# Spresense_PLC__V1.net
KiCad netlist of a schematic drawn in EAGLE
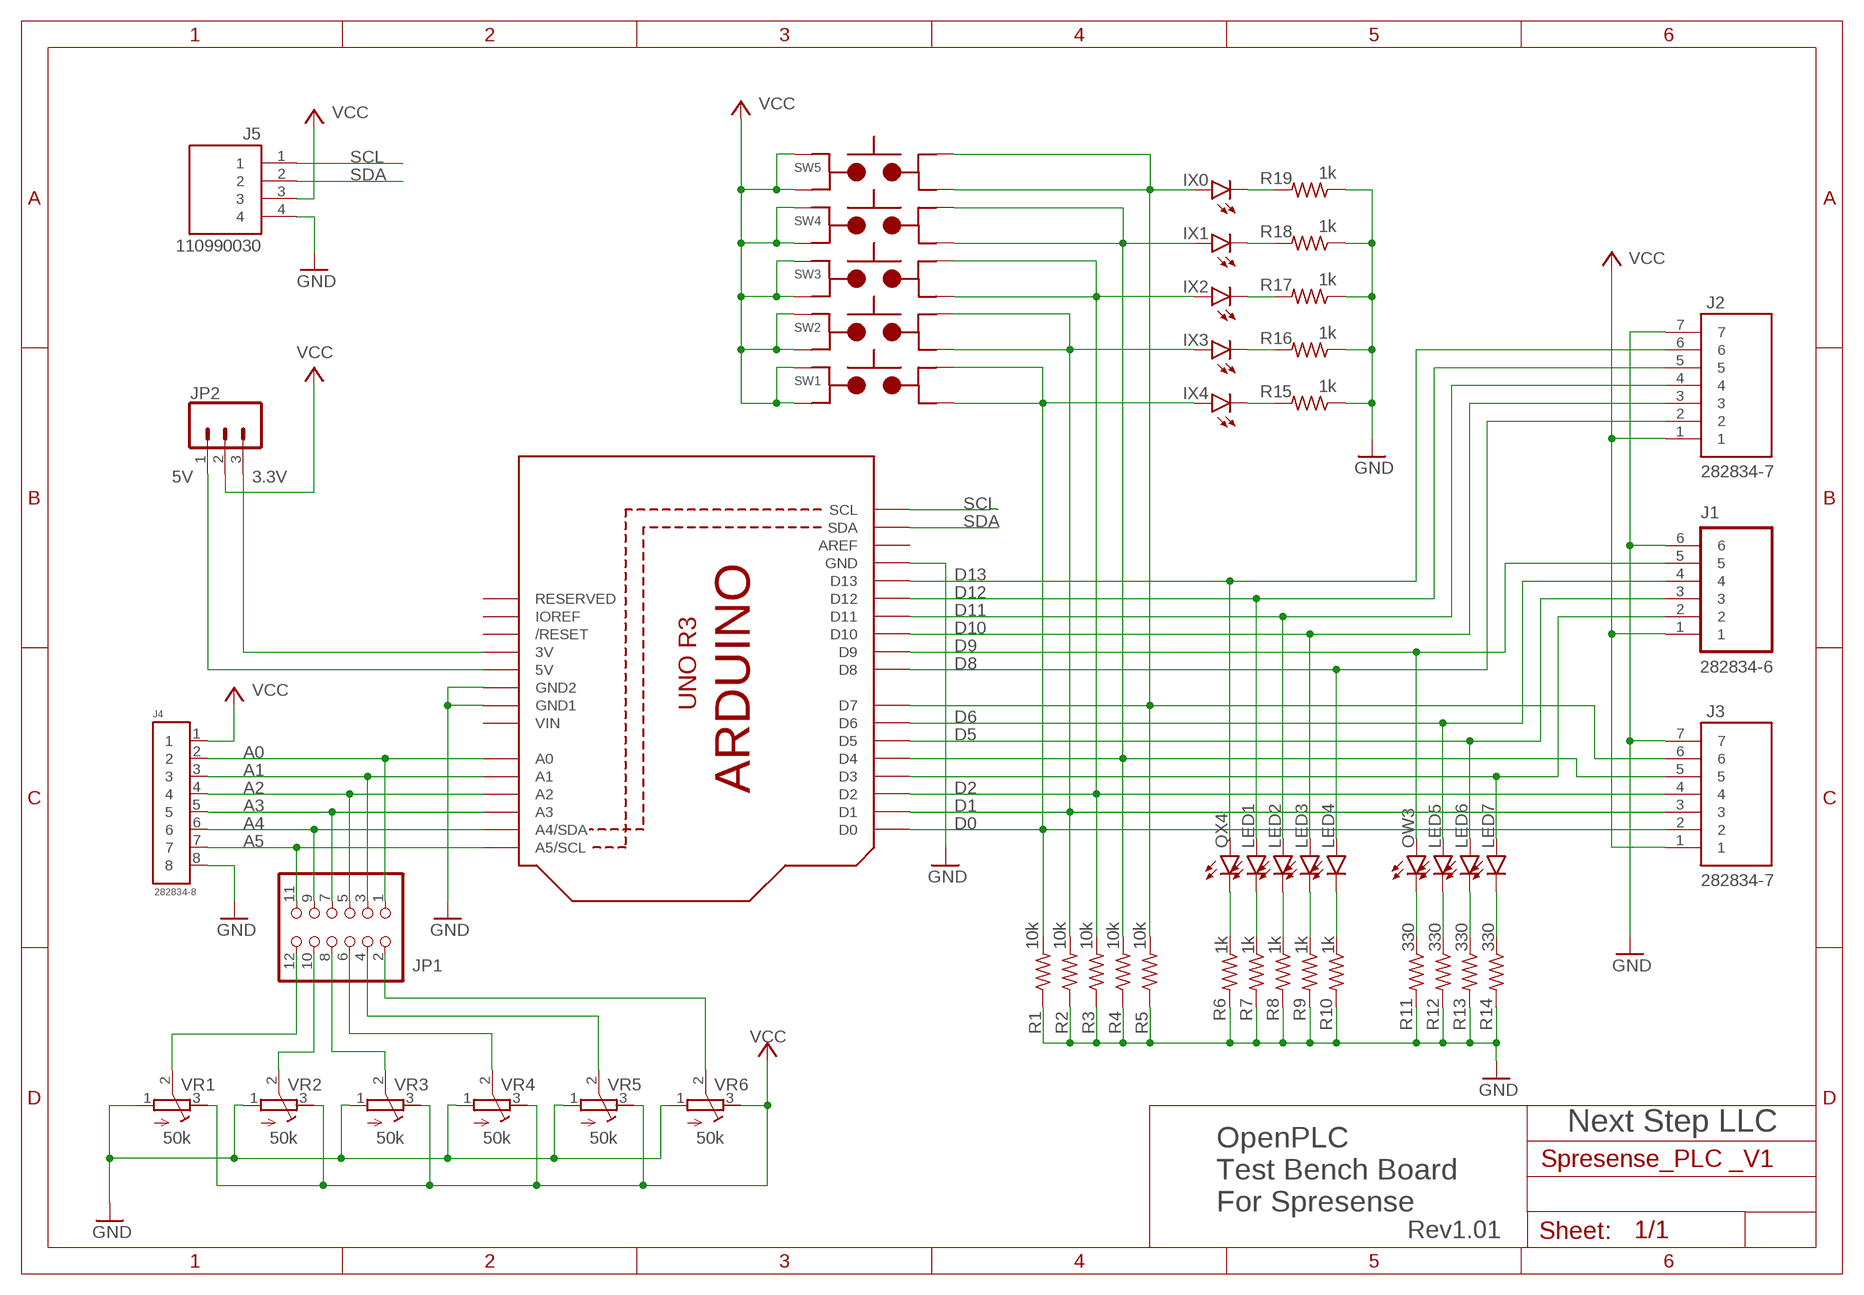
[diagram p0: schematic, sheet 1]

(export (version "E")
  (design (tool "Eeschema 10.0.6"))
  (components
    (comp (ref "IX0")
      (value "LEDCHIP-LED0603")
      (footprint "eagle-import:CHIP-LED0603")
      (libsource (lib "eagle-import") (part "LEDCHIP-LED0603"))
    )
    (comp (ref "IX1")
      (value "LEDCHIP-LED0603")
      (footprint "eagle-import:CHIP-LED0603")
      (libsource (lib "eagle-import") (part "LEDCHIP-LED0603"))
    )
    (comp (ref "IX2")
      (value "LEDCHIP-LED0603")
      (footprint "eagle-import:CHIP-LED0603")
      (libsource (lib "eagle-import") (part "LEDCHIP-LED0603"))
    )
    (comp (ref "IX3")
      (value "LEDCHIP-LED0603")
      (footprint "eagle-import:CHIP-LED0603")
      (libsource (lib "eagle-import") (part "LEDCHIP-LED0603"))
    )
    (comp (ref "IX4")
      (value "LEDCHIP-LED0603")
      (footprint "eagle-import:CHIP-LED0603")
      (libsource (lib "eagle-import") (part "LEDCHIP-LED0603"))
    )
    (comp (ref "J1")
      (value "282834-6")
      (footprint "eagle-import:TE_282834-6")
      (fields (field (name "MF") "TE Connectivity"))
      (libsource (lib "eagle-import") (part "282834-6"))
    )
    (comp (ref "J2")
      (value "282834-7")
      (footprint "eagle-import:TE_282834-7")
      (fields (field (name "MF") "TE Connectivity"))
      (libsource (lib "eagle-import") (part "282834-7"))
    )
    (comp (ref "J3")
      (value "282834-7")
      (footprint "eagle-import:TE_282834-7")
      (fields (field (name "MF") "TE Connectivity"))
      (libsource (lib "eagle-import") (part "282834-7"))
    )
    (comp (ref "J4")
      (value "282834-8")
      (footprint "eagle-import:HDRV8W85P254_8X1_2078X650X1000")
      (fields (field (name "MF") "TE Connectivity"))
      (libsource (lib "eagle-import") (part "282834-8"))
    )
    (comp (ref "J5")
      (value "110990030")
      (footprint "eagle-import:SEEED_110990030")
      (fields (field (name "MF") "Seeed Technology Co., Ltd"))
      (libsource (lib "eagle-import") (part "110990030"))
    )
    (comp (ref "JP1")
      (value "PINHD-2X6")
      (footprint "eagle-import:2X06")
      (libsource (lib "eagle-import") (part "PINHD-2X6"))
    )
    (comp (ref "JP2")
      (value "455-1750-1-ND")
      (footprint "eagle-import:1X03")
      (libsource (lib "eagle-import") (part "CONN_03"))
    )
    (comp (ref "LED1")
      (value "LEDCHIP-LED0603")
      (footprint "eagle-import:CHIP-LED0603")
      (libsource (lib "eagle-import") (part "LEDCHIP-LED0603"))
    )
    (comp (ref "LED2")
      (value "LEDCHIP-LED0603")
      (footprint "eagle-import:CHIP-LED0603")
      (libsource (lib "eagle-import") (part "LEDCHIP-LED0603"))
    )
    (comp (ref "LED3")
      (value "LEDCHIP-LED0603")
      (footprint "eagle-import:CHIP-LED0603")
      (libsource (lib "eagle-import") (part "LEDCHIP-LED0603"))
    )
    (comp (ref "LED4")
      (value "LEDCHIP-LED0603")
      (footprint "eagle-import:CHIP-LED0603")
      (libsource (lib "eagle-import") (part "LEDCHIP-LED0603"))
    )
    (comp (ref "LED5")
      (value "LEDCHIP-LED0603")
      (footprint "eagle-import:CHIP-LED0603")
      (libsource (lib "eagle-import") (part "LEDCHIP-LED0603"))
    )
    (comp (ref "LED6")
      (value "LEDCHIP-LED0603")
      (footprint "eagle-import:CHIP-LED0603")
      (libsource (lib "eagle-import") (part "LEDCHIP-LED0603"))
    )
    (comp (ref "LED7")
      (value "LEDCHIP-LED0603")
      (footprint "eagle-import:CHIP-LED0603")
      (libsource (lib "eagle-import") (part "LEDCHIP-LED0603"))
    )
    (comp (ref "OW3")
      (value "LEDCHIP-LED0603")
      (footprint "eagle-import:CHIP-LED0603")
      (libsource (lib "eagle-import") (part "LEDCHIP-LED0603"))
    )
    (comp (ref "QX4")
      (value "LEDCHIP-LED0603")
      (footprint "eagle-import:CHIP-LED0603")
      (libsource (lib "eagle-import") (part "LEDCHIP-LED0603"))
    )
    (comp (ref "R1")
      (value "10k")
      (footprint "eagle-import:R0603")
      (libsource (lib "eagle-import") (part "R-US_R0603"))
    )
    (comp (ref "R2")
      (value "10k")
      (footprint "eagle-import:R0603")
      (libsource (lib "eagle-import") (part "R-US_R0603"))
    )
    (comp (ref "R3")
      (value "10k")
      (footprint "eagle-import:R0603")
      (libsource (lib "eagle-import") (part "R-US_R0603"))
    )
    (comp (ref "R4")
      (value "10k")
      (footprint "eagle-import:R0603")
      (libsource (lib "eagle-import") (part "R-US_R0603"))
    )
    (comp (ref "R5")
      (value "10k")
      (footprint "eagle-import:R0603")
      (libsource (lib "eagle-import") (part "R-US_R0603"))
    )
    (comp (ref "R6")
      (value "1k")
      (footprint "eagle-import:R0603")
      (libsource (lib "eagle-import") (part "R-US_R0603"))
    )
    (comp (ref "R7")
      (value "1k")
      (footprint "eagle-import:R0603")
      (libsource (lib "eagle-import") (part "R-US_R0603"))
    )
    (comp (ref "R8")
      (value "1k")
      (footprint "eagle-import:R0603")
      (libsource (lib "eagle-import") (part "R-US_R0603"))
    )
    (comp (ref "R9")
      (value "1k")
      (footprint "eagle-import:R0603")
      (libsource (lib "eagle-import") (part "R-US_R0603"))
    )
    (comp (ref "R10")
      (value "1k")
      (footprint "eagle-import:R0603")
      (libsource (lib "eagle-import") (part "R-US_R0603"))
    )
    (comp (ref "R11")
      (value "330")
      (footprint "eagle-import:R0603")
      (libsource (lib "eagle-import") (part "R-US_R0603"))
    )
    (comp (ref "R12")
      (value "330")
      (footprint "eagle-import:R0603")
      (libsource (lib "eagle-import") (part "R-US_R0603"))
    )
    (comp (ref "R13")
      (value "330")
      (footprint "eagle-import:R0603")
      (libsource (lib "eagle-import") (part "R-US_R0603"))
    )
    (comp (ref "R14")
      (value "330")
      (footprint "eagle-import:R0603")
      (libsource (lib "eagle-import") (part "R-US_R0603"))
    )
    (comp (ref "R15")
      (value "1k")
      (footprint "eagle-import:R0603")
      (libsource (lib "eagle-import") (part "R-US_R0603"))
    )
    (comp (ref "R16")
      (value "1k")
      (footprint "eagle-import:R0603")
      (libsource (lib "eagle-import") (part "R-US_R0603"))
    )
    (comp (ref "R17")
      (value "1k")
      (footprint "eagle-import:R0603")
      (libsource (lib "eagle-import") (part "R-US_R0603"))
    )
    (comp (ref "R18")
      (value "1k")
      (footprint "eagle-import:R0603")
      (libsource (lib "eagle-import") (part "R-US_R0603"))
    )
    (comp (ref "R19")
      (value "1k")
      (footprint "eagle-import:R0603")
      (libsource (lib "eagle-import") (part "R-US_R0603"))
    )
    (comp (ref "SW1")
      (value "TL3342F160QG/TR")
      (footprint "eagle-import:SW_TL3342F160QG_TR")
      (fields (field (name "MF") "E-Switch"))
      (libsource (lib "eagle-import") (part "TL3342F160QG/TR"))
    )
    (comp (ref "SW2")
      (value "TL3342F160QG/TR")
      (footprint "eagle-import:SW_TL3342F160QG_TR")
      (fields (field (name "MF") "E-Switch"))
      (libsource (lib "eagle-import") (part "TL3342F160QG/TR"))
    )
    (comp (ref "SW3")
      (value "TL3342F160QG/TR")
      (footprint "eagle-import:SW_TL3342F160QG_TR")
      (fields (field (name "MF") "E-Switch"))
      (libsource (lib "eagle-import") (part "TL3342F160QG/TR"))
    )
    (comp (ref "SW4")
      (value "TL3342F160QG/TR")
      (footprint "eagle-import:SW_TL3342F160QG_TR")
      (fields (field (name "MF") "E-Switch"))
      (libsource (lib "eagle-import") (part "TL3342F160QG/TR"))
    )
    (comp (ref "SW5")
      (value "TL3342F160QG/TR")
      (footprint "eagle-import:SW_TL3342F160QG_TR")
      (fields (field (name "MF") "E-Switch"))
      (libsource (lib "eagle-import") (part "TL3342F160QG/TR"))
    )
    (comp (ref "U1")
      (value "ARDUINOR3-DIMENSION")
      (footprint "eagle-import:ARDUINOR3")
      (libsource (lib "eagle-import") (part "ARDUINOR3-DIMENSION"))
    )
    (comp (ref "VR1")
      (value "50k")
      (footprint "eagle-import:RTRIM3339P")
      (libsource (lib "eagle-import") (part "R-TRIMM3339P"))
    )
    (comp (ref "VR2")
      (value "50k")
      (footprint "eagle-import:RTRIM3339P")
      (libsource (lib "eagle-import") (part "R-TRIMM3339P"))
    )
    (comp (ref "VR3")
      (value "50k")
      (footprint "eagle-import:RTRIM3339P")
      (libsource (lib "eagle-import") (part "R-TRIMM3339P"))
    )
    (comp (ref "VR4")
      (value "50k")
      (footprint "eagle-import:RTRIM3339P")
      (libsource (lib "eagle-import") (part "R-TRIMM3339P"))
    )
    (comp (ref "VR5")
      (value "50k")
      (footprint "eagle-import:RTRIM3339P")
      (libsource (lib "eagle-import") (part "R-TRIMM3339P"))
    )
    (comp (ref "VR6")
      (value "50k")
      (footprint "eagle-import:RTRIM3339P")
      (libsource (lib "eagle-import") (part "R-TRIMM3339P"))
    )
  )
  (nets
    (net (code "1") (name "/A0") (class "Default")
      (node (ref "J4") (pin "2") (pinfunction "2_2") (pintype "passive"))
      (node (ref "JP1") (pin "1") (pinfunction "1_1") (pintype "passive"))
      (node (ref "U1") (pin "A0") (pinfunction "A0_A0") (pintype "bidirectional"))
    )
    (net (code "2") (name "/A1") (class "Default")
      (node (ref "J4") (pin "3") (pinfunction "3_3") (pintype "passive"))
      (node (ref "JP1") (pin "3") (pinfunction "3_3") (pintype "passive"))
      (node (ref "U1") (pin "A1") (pinfunction "A1_A1") (pintype "bidirectional"))
    )
    (net (code "3") (name "/A2") (class "Default")
      (node (ref "J4") (pin "4") (pinfunction "4_4") (pintype "passive"))
      (node (ref "JP1") (pin "5") (pinfunction "5_5") (pintype "passive"))
      (node (ref "U1") (pin "A2") (pinfunction "A2_A2") (pintype "bidirectional"))
    )
    (net (code "4") (name "/A3") (class "Default")
      (node (ref "J4") (pin "5") (pinfunction "5_5") (pintype "passive"))
      (node (ref "JP1") (pin "7") (pinfunction "7_7") (pintype "passive"))
      (node (ref "U1") (pin "A3") (pinfunction "A3_A3") (pintype "bidirectional"))
    )
    (net (code "5") (name "/A4") (class "Default")
      (node (ref "J4") (pin "6") (pinfunction "6_6") (pintype "passive"))
      (node (ref "JP1") (pin "9") (pinfunction "9_9") (pintype "passive"))
      (node (ref "U1") (pin "A4") (pinfunction "A4/SDA_A4") (pintype "bidirectional"))
    )
    (net (code "6") (name "/A5") (class "Default")
      (node (ref "J4") (pin "7") (pinfunction "7_7") (pintype "passive"))
      (node (ref "JP1") (pin "11") (pinfunction "11_11") (pintype "passive"))
      (node (ref "U1") (pin "A5") (pinfunction "A5/SCL_A5") (pintype "bidirectional"))
    )
    (net (code "7") (name "/D0") (class "Default")
      (node (ref "IX4") (pin "A") (pinfunction "A_A") (pintype "passive"))
      (node (ref "J3") (pin "2") (pinfunction "2_2") (pintype "passive"))
      (node (ref "R1") (pin "2") (pinfunction "2_2") (pintype "passive"))
      (node (ref "SW1") (pin "1") (pinfunction "1_1") (pintype "passive"))
      (node (ref "SW1") (pin "2") (pinfunction "2_2") (pintype "passive"))
      (node (ref "U1") (pin "D0") (pinfunction "D0_D0") (pintype "bidirectional"))
    )
    (net (code "8") (name "/D1") (class "Default")
      (node (ref "IX3") (pin "A") (pinfunction "A_A") (pintype "passive"))
      (node (ref "J3") (pin "3") (pinfunction "3_3") (pintype "passive"))
      (node (ref "R2") (pin "2") (pinfunction "2_2") (pintype "passive"))
      (node (ref "SW2") (pin "1") (pinfunction "1_1") (pintype "passive"))
      (node (ref "SW2") (pin "2") (pinfunction "2_2") (pintype "passive"))
      (node (ref "U1") (pin "D1") (pinfunction "D1_D1") (pintype "bidirectional"))
    )
    (net (code "9") (name "/D2") (class "Default")
      (node (ref "IX2") (pin "A") (pinfunction "A_A") (pintype "passive"))
      (node (ref "J3") (pin "4") (pinfunction "4_4") (pintype "passive"))
      (node (ref "R3") (pin "2") (pinfunction "2_2") (pintype "passive"))
      (node (ref "SW3") (pin "1") (pinfunction "1_1") (pintype "passive"))
      (node (ref "SW3") (pin "2") (pinfunction "2_2") (pintype "passive"))
      (node (ref "U1") (pin "D2") (pinfunction "D2_D2") (pintype "bidirectional"))
    )
    (net (code "10") (name "/D5") (class "Default")
      (node (ref "IX1") (pin "A") (pinfunction "A_A") (pintype "passive"))
      (node (ref "J3") (pin "5") (pinfunction "5_5") (pintype "passive"))
      (node (ref "R4") (pin "2") (pinfunction "2_2") (pintype "passive"))
      (node (ref "SW4") (pin "1") (pinfunction "1_1") (pintype "passive"))
      (node (ref "SW4") (pin "2") (pinfunction "2_2") (pintype "passive"))
      (node (ref "U1") (pin "D4") (pinfunction "D4_D4") (pintype "bidirectional"))
    )
    (net (code "11") (name "/D6") (class "Default")
      (node (ref "IX0") (pin "A") (pinfunction "A_A") (pintype "passive"))
      (node (ref "J3") (pin "6") (pinfunction "6_6") (pintype "passive"))
      (node (ref "R5") (pin "2") (pinfunction "2_2") (pintype "passive"))
      (node (ref "SW5") (pin "1") (pinfunction "1_1") (pintype "passive"))
      (node (ref "SW5") (pin "2") (pinfunction "2_2") (pintype "passive"))
      (node (ref "U1") (pin "D7") (pinfunction "D7_D7") (pintype "bidirectional"))
    )
    (net (code "12") (name "/D8") (class "Default")
      (node (ref "J2") (pin "2") (pinfunction "2_2") (pintype "passive"))
      (node (ref "LED4") (pin "A") (pinfunction "A_A") (pintype "passive"))
      (node (ref "U1") (pin "D8") (pinfunction "D8_D8") (pintype "bidirectional"))
    )
    (net (code "13") (name "/D9") (class "Default")
      (node (ref "J1") (pin "5") (pinfunction "5_5") (pintype "passive"))
      (node (ref "OW3") (pin "A") (pinfunction "A_A") (pintype "passive"))
      (node (ref "U1") (pin "D9") (pinfunction "D9_D9") (pintype "bidirectional"))
    )
    (net (code "14") (name "/D10") (class "Default")
      (node (ref "J2") (pin "3") (pinfunction "3_3") (pintype "passive"))
      (node (ref "LED3") (pin "A") (pinfunction "A_A") (pintype "passive"))
      (node (ref "U1") (pin "D10") (pinfunction "D10_D10") (pintype "bidirectional"))
    )
    (net (code "15") (name "/D11") (class "Default")
      (node (ref "J2") (pin "4") (pinfunction "4_4") (pintype "passive"))
      (node (ref "LED2") (pin "A") (pinfunction "A_A") (pintype "passive"))
      (node (ref "U1") (pin "D11") (pinfunction "D11_D11") (pintype "bidirectional"))
    )
    (net (code "16") (name "/D12") (class "Default")
      (node (ref "J2") (pin "5") (pinfunction "5_5") (pintype "passive"))
      (node (ref "LED1") (pin "A") (pinfunction "A_A") (pintype "passive"))
      (node (ref "U1") (pin "D12") (pinfunction "D12_D12") (pintype "bidirectional"))
    )
    (net (code "17") (name "/D13") (class "Default")
      (node (ref "J2") (pin "6") (pinfunction "6_6") (pintype "passive"))
      (node (ref "QX4") (pin "A") (pinfunction "A_A") (pintype "passive"))
      (node (ref "U1") (pin "D13") (pinfunction "D13_D13") (pintype "bidirectional"))
    )
    (net (code "18") (name "/SCL") (class "Default")
      (node (ref "J5") (pin "1") (pinfunction "1_1") (pintype "passive"))
      (node (ref "U1") (pin "SCL") (pinfunction "SCL_SCL") (pintype "bidirectional"))
    )
    (net (code "19") (name "/SDA") (class "Default")
      (node (ref "J5") (pin "2") (pinfunction "2_2") (pintype "passive"))
      (node (ref "U1") (pin "SDA") (pinfunction "SDA_SDA") (pintype "bidirectional"))
    )
    (net (code "20") (name "/VIN") (class "Default")
      (node (ref "U1") (pin "VIN") (pinfunction "VIN_VIN") (pintype "power_in"))
    )
    (net (code "21") (name "GND") (class "Default")
      (node (ref "J1") (pin "6") (pinfunction "6_6") (pintype "passive"))
      (node (ref "J2") (pin "7") (pinfunction "7_7") (pintype "passive"))
      (node (ref "J3") (pin "7") (pinfunction "7_7") (pintype "passive"))
      (node (ref "J4") (pin "8") (pinfunction "8_8") (pintype "passive"))
      (node (ref "J5") (pin "4") (pinfunction "4_4") (pintype "passive"))
      (node (ref "R1") (pin "1") (pinfunction "1_1") (pintype "passive"))
      (node (ref "R10") (pin "2") (pinfunction "2_2") (pintype "passive"))
      (node (ref "R11") (pin "2") (pinfunction "2_2") (pintype "passive"))
      (node (ref "R12") (pin "2") (pinfunction "2_2") (pintype "passive"))
      (node (ref "R13") (pin "2") (pinfunction "2_2") (pintype "passive"))
      (node (ref "R14") (pin "2") (pinfunction "2_2") (pintype "passive"))
      (node (ref "R15") (pin "1") (pinfunction "1_1") (pintype "passive"))
      (node (ref "R16") (pin "1") (pinfunction "1_1") (pintype "passive"))
      (node (ref "R17") (pin "1") (pinfunction "1_1") (pintype "passive"))
      (node (ref "R18") (pin "1") (pinfunction "1_1") (pintype "passive"))
      (node (ref "R19") (pin "1") (pinfunction "1_1") (pintype "passive"))
      (node (ref "R2") (pin "1") (pinfunction "1_1") (pintype "passive"))
      (node (ref "R3") (pin "1") (pinfunction "1_1") (pintype "passive"))
      (node (ref "R4") (pin "1") (pinfunction "1_1") (pintype "passive"))
      (node (ref "R5") (pin "1") (pinfunction "1_1") (pintype "passive"))
      (node (ref "R6") (pin "2") (pinfunction "2_2") (pintype "passive"))
      (node (ref "R7") (pin "2") (pinfunction "2_2") (pintype "passive"))
      (node (ref "R8") (pin "2") (pinfunction "2_2") (pintype "passive"))
      (node (ref "R9") (pin "2") (pinfunction "2_2") (pintype "passive"))
      (node (ref "U1") (pin "GND") (pinfunction "GND_GND") (pintype "power_in"))
      (node (ref "U1") (pin "GND1") (pinfunction "GND1_GND1") (pintype "power_in"))
      (node (ref "U1") (pin "GND2") (pinfunction "GND2_GND2") (pintype "power_in"))
      (node (ref "VR1") (pin "1") (pinfunction "A_1") (pintype "passive"))
      (node (ref "VR2") (pin "1") (pinfunction "A_1") (pintype "passive"))
      (node (ref "VR3") (pin "1") (pinfunction "A_1") (pintype "passive"))
      (node (ref "VR4") (pin "1") (pinfunction "A_1") (pintype "passive"))
      (node (ref "VR5") (pin "1") (pinfunction "A_1") (pintype "passive"))
      (node (ref "VR6") (pin "1") (pinfunction "A_1") (pintype "passive"))
    )
    (net (code "22") (name "Net-(IX0-PadC)") (class "Default")
      (node (ref "IX0") (pin "C") (pinfunction "C_C") (pintype "passive"))
      (node (ref "R19") (pin "2") (pinfunction "2_2") (pintype "passive"))
    )
    (net (code "23") (name "Net-(IX1-PadC)") (class "Default")
      (node (ref "IX1") (pin "C") (pinfunction "C_C") (pintype "passive"))
      (node (ref "R18") (pin "2") (pinfunction "2_2") (pintype "passive"))
    )
    (net (code "24") (name "Net-(IX2-PadC)") (class "Default")
      (node (ref "IX2") (pin "C") (pinfunction "C_C") (pintype "passive"))
      (node (ref "R17") (pin "2") (pinfunction "2_2") (pintype "passive"))
    )
    (net (code "25") (name "Net-(IX3-PadC)") (class "Default")
      (node (ref "IX3") (pin "C") (pinfunction "C_C") (pintype "passive"))
      (node (ref "R16") (pin "2") (pinfunction "2_2") (pintype "passive"))
    )
    (net (code "26") (name "Net-(IX4-PadC)") (class "Default")
      (node (ref "IX4") (pin "C") (pinfunction "C_C") (pintype "passive"))
      (node (ref "R15") (pin "2") (pinfunction "2_2") (pintype "passive"))
    )
    (net (code "27") (name "Net-(J1-Pad2)") (class "Default")
      (node (ref "J1") (pin "2") (pinfunction "2_2") (pintype "passive"))
      (node (ref "LED7") (pin "A") (pinfunction "A_A") (pintype "passive"))
      (node (ref "U1") (pin "D3") (pinfunction "D3_D3") (pintype "bidirectional"))
    )
    (net (code "28") (name "Net-(J1-Pad3)") (class "Default")
      (node (ref "J1") (pin "3") (pinfunction "3_3") (pintype "passive"))
      (node (ref "LED6") (pin "A") (pinfunction "A_A") (pintype "passive"))
      (node (ref "U1") (pin "D5") (pinfunction "D5_D5") (pintype "bidirectional"))
    )
    (net (code "29") (name "Net-(J1-Pad4)") (class "Default")
      (node (ref "J1") (pin "4") (pinfunction "4_4") (pintype "passive"))
      (node (ref "LED5") (pin "A") (pinfunction "A_A") (pintype "passive"))
      (node (ref "U1") (pin "D6") (pinfunction "D6_D6") (pintype "bidirectional"))
    )
    (net (code "30") (name "Net-(JP2-Pad1)") (class "Default")
      (node (ref "JP2") (pin "1") (pinfunction "1_1") (pintype "passive"))
      (node (ref "U1") (pin "5V") (pinfunction "5V_5V") (pintype "power_in"))
    )
    (net (code "31") (name "Net-(JP2-Pad3)") (class "Default")
      (node (ref "JP2") (pin "3") (pinfunction "3_3") (pintype "passive"))
      (node (ref "U1") (pin "3V") (pinfunction "3V_3V") (pintype "power_in"))
    )
    (net (code "32") (name "Net-(LED1-PadC)") (class "Default")
      (node (ref "LED1") (pin "C") (pinfunction "C_C") (pintype "passive"))
      (node (ref "R7") (pin "1") (pinfunction "1_1") (pintype "passive"))
    )
    (net (code "33") (name "Net-(LED2-PadC)") (class "Default")
      (node (ref "LED2") (pin "C") (pinfunction "C_C") (pintype "passive"))
      (node (ref "R8") (pin "1") (pinfunction "1_1") (pintype "passive"))
    )
    (net (code "34") (name "Net-(LED3-PadC)") (class "Default")
      (node (ref "LED3") (pin "C") (pinfunction "C_C") (pintype "passive"))
      (node (ref "R9") (pin "1") (pinfunction "1_1") (pintype "passive"))
    )
    (net (code "35") (name "Net-(LED4-PadC)") (class "Default")
      (node (ref "LED4") (pin "C") (pinfunction "C_C") (pintype "passive"))
      (node (ref "R10") (pin "1") (pinfunction "1_1") (pintype "passive"))
    )
    (net (code "36") (name "Net-(LED5-PadC)") (class "Default")
      (node (ref "LED5") (pin "C") (pinfunction "C_C") (pintype "passive"))
      (node (ref "R12") (pin "1") (pinfunction "1_1") (pintype "passive"))
    )
    (net (code "37") (name "Net-(LED6-PadC)") (class "Default")
      (node (ref "LED6") (pin "C") (pinfunction "C_C") (pintype "passive"))
      (node (ref "R13") (pin "1") (pinfunction "1_1") (pintype "passive"))
    )
    (net (code "38") (name "Net-(LED7-PadC)") (class "Default")
      (node (ref "LED7") (pin "C") (pinfunction "C_C") (pintype "passive"))
      (node (ref "R14") (pin "1") (pinfunction "1_1") (pintype "passive"))
    )
    (net (code "39") (name "Net-(OW3-PadC)") (class "Default")
      (node (ref "OW3") (pin "C") (pinfunction "C_C") (pintype "passive"))
      (node (ref "R11") (pin "1") (pinfunction "1_1") (pintype "passive"))
    )
    (net (code "40") (name "Net-(QX4-PadC)") (class "Default")
      (node (ref "QX4") (pin "C") (pinfunction "C_C") (pintype "passive"))
      (node (ref "R6") (pin "1") (pinfunction "1_1") (pintype "passive"))
    )
    (net (code "41") (name "Net-(VR1-S)") (class "Default")
      (node (ref "JP1") (pin "12") (pinfunction "12_12") (pintype "passive"))
      (node (ref "VR1") (pin "2") (pinfunction "S_2") (pintype "passive"))
    )
    (net (code "42") (name "Net-(VR2-S)") (class "Default")
      (node (ref "JP1") (pin "10") (pinfunction "10_10") (pintype "passive"))
      (node (ref "VR2") (pin "2") (pinfunction "S_2") (pintype "passive"))
    )
    (net (code "43") (name "Net-(VR3-S)") (class "Default")
      (node (ref "JP1") (pin "8") (pinfunction "8_8") (pintype "passive"))
      (node (ref "VR3") (pin "2") (pinfunction "S_2") (pintype "passive"))
    )
    (net (code "44") (name "Net-(VR4-S)") (class "Default")
      (node (ref "JP1") (pin "6") (pinfunction "6_6") (pintype "passive"))
      (node (ref "VR4") (pin "2") (pinfunction "S_2") (pintype "passive"))
    )
    (net (code "45") (name "Net-(VR5-S)") (class "Default")
      (node (ref "JP1") (pin "4") (pinfunction "4_4") (pintype "passive"))
      (node (ref "VR5") (pin "2") (pinfunction "S_2") (pintype "passive"))
    )
    (net (code "46") (name "Net-(VR6-S)") (class "Default")
      (node (ref "JP1") (pin "2") (pinfunction "2_2") (pintype "passive"))
      (node (ref "VR6") (pin "2") (pinfunction "S_2") (pintype "passive"))
    )
    (net (code "47") (name "VCC") (class "Default")
      (node (ref "J1") (pin "1") (pinfunction "1_1") (pintype "passive"))
      (node (ref "J2") (pin "1") (pinfunction "1_1") (pintype "passive"))
      (node (ref "J3") (pin "1") (pinfunction "1_1") (pintype "passive"))
      (node (ref "J4") (pin "1") (pinfunction "1_1") (pintype "passive"))
      (node (ref "J5") (pin "3") (pinfunction "3_3") (pintype "passive"))
      (node (ref "JP2") (pin "2") (pinfunction "2_2") (pintype "passive"))
      (node (ref "SW1") (pin "3") (pinfunction "3_3") (pintype "passive"))
      (node (ref "SW1") (pin "4") (pinfunction "4_4") (pintype "passive"))
      (node (ref "SW2") (pin "3") (pinfunction "3_3") (pintype "passive"))
      (node (ref "SW2") (pin "4") (pinfunction "4_4") (pintype "passive"))
      (node (ref "SW3") (pin "3") (pinfunction "3_3") (pintype "passive"))
      (node (ref "SW3") (pin "4") (pinfunction "4_4") (pintype "passive"))
      (node (ref "SW4") (pin "3") (pinfunction "3_3") (pintype "passive"))
      (node (ref "SW4") (pin "4") (pinfunction "4_4") (pintype "passive"))
      (node (ref "SW5") (pin "3") (pinfunction "3_3") (pintype "passive"))
      (node (ref "SW5") (pin "4") (pinfunction "4_4") (pintype "passive"))
      (node (ref "VR1") (pin "3") (pinfunction "E_3") (pintype "passive"))
      (node (ref "VR2") (pin "3") (pinfunction "E_3") (pintype "passive"))
      (node (ref "VR3") (pin "3") (pinfunction "E_3") (pintype "passive"))
      (node (ref "VR4") (pin "3") (pinfunction "E_3") (pintype "passive"))
      (node (ref "VR5") (pin "3") (pinfunction "E_3") (pintype "passive"))
      (node (ref "VR6") (pin "3") (pinfunction "E_3") (pintype "passive"))
    )
    (net (code "48") (name "unconnected-(U1-PadAREF)") (class "Default")
      (node (ref "U1") (pin "AREF") (pinfunction "AREF_AREF") (pintype "bidirectional"))
    )
    (net (code "49") (name "unconnected-(U1-PadIOREF)") (class "Default")
      (node (ref "U1") (pin "IOREF") (pinfunction "IOREF_IOREF") (pintype "output"))
    )
    (net (code "50") (name "unconnected-(U1-PadRESERVED)") (class "Default")
      (node (ref "U1") (pin "RESERVED") (pinfunction "RESERVED_RESERVED") (pintype "no_connect"))
    )
    (net (code "51") (name "unconnected-(U1-{slash}RESET-PadRESET)") (class "Default")
      (node (ref "U1") (pin "RESET") (pinfunction "/RESET_RESET") (pintype "bidirectional"))
    )
  )
)
